# main_board3.net
KiCad netlist of a schematic drawn in EAGLE
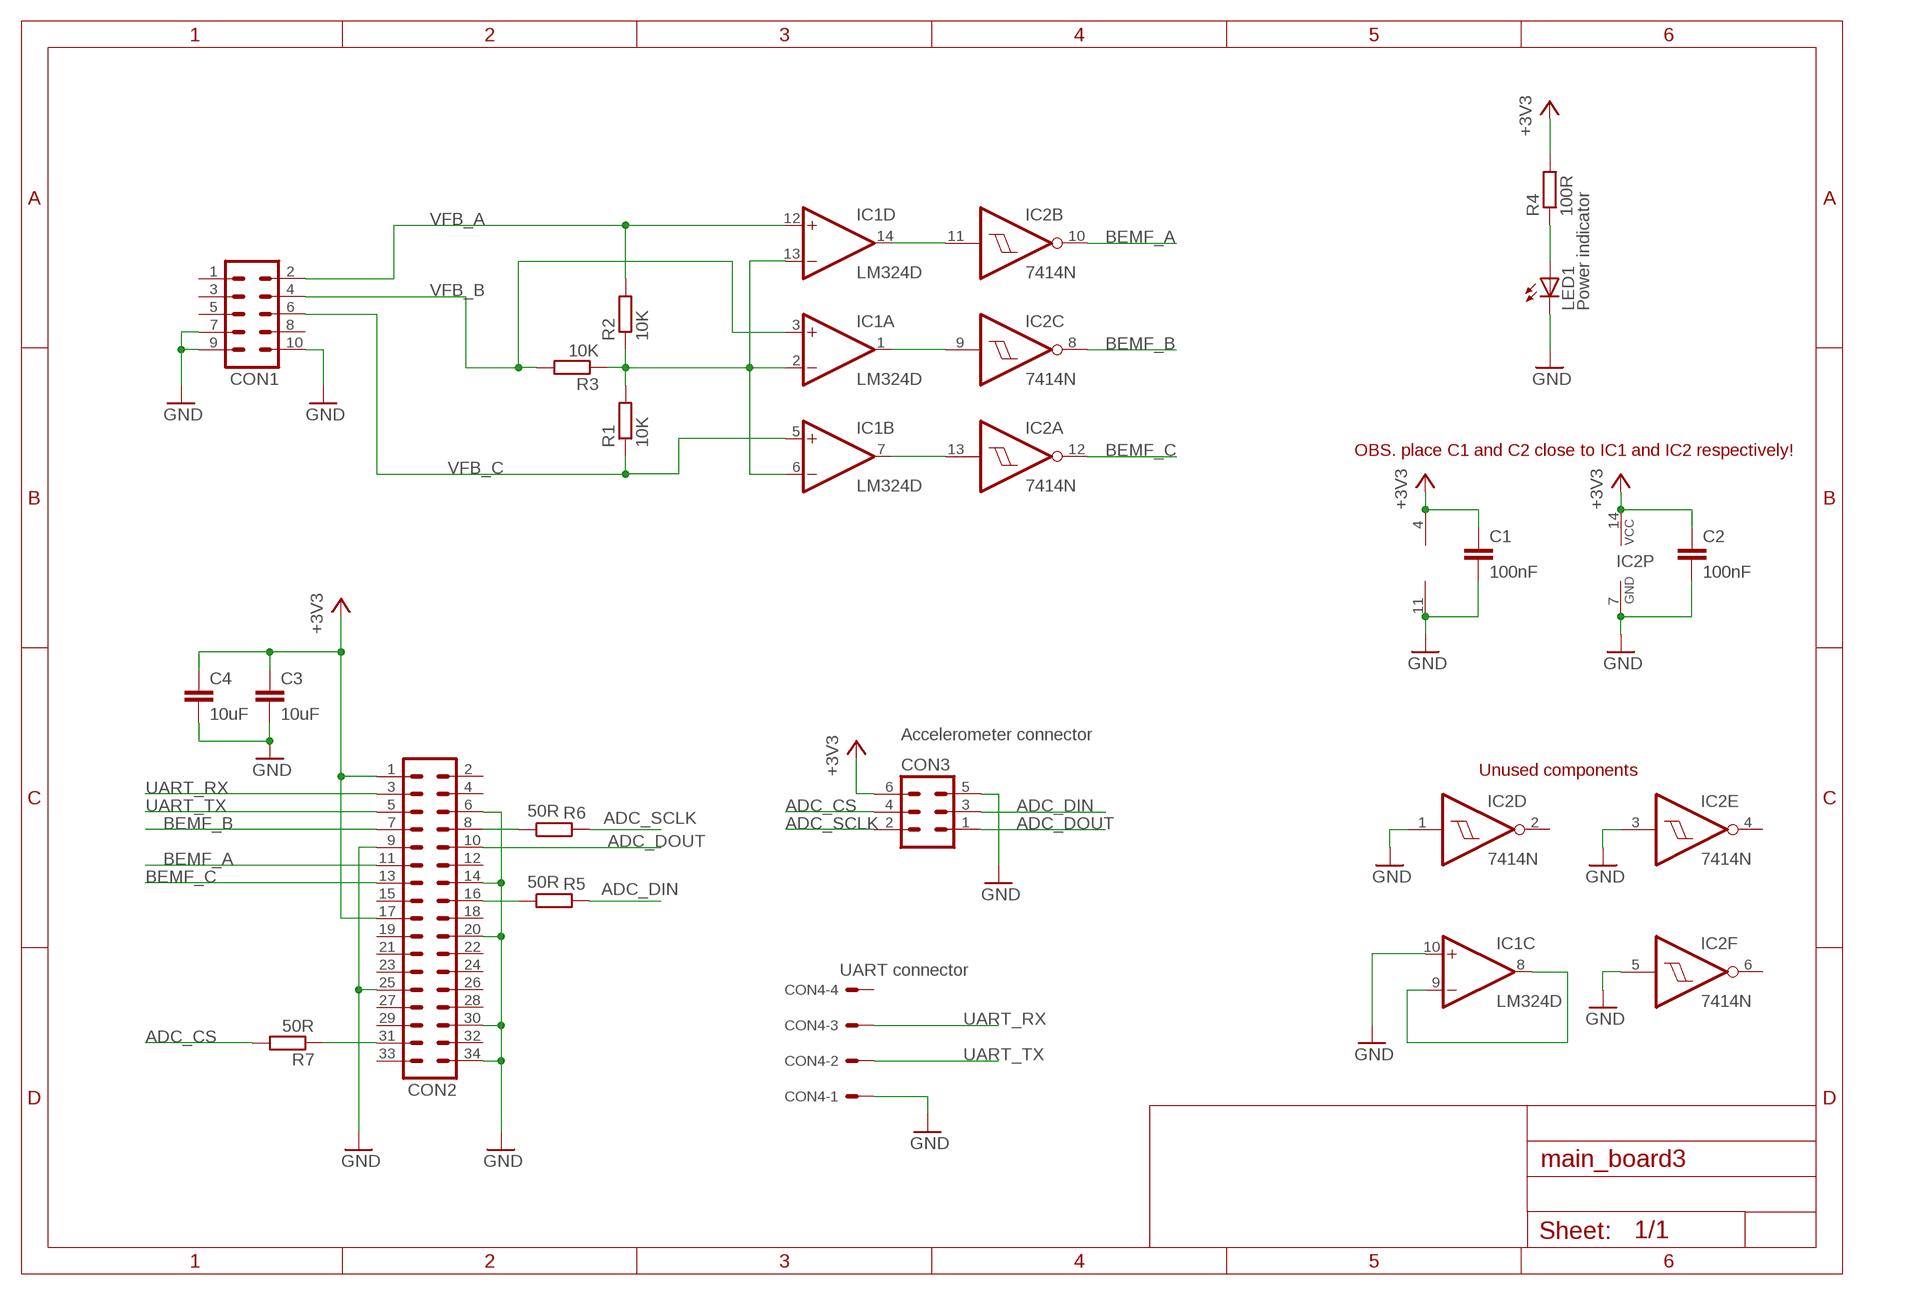
[diagram p0: schematic, sheet 1]

(export (version "E")
  (design (tool "Eeschema 10.0.6"))
  (components
    (comp (ref "C1")
      (value "100nF")
      (footprint "eagle-import:C0805K")
      (libsource (lib "eagle-import") (part "C-EUC0805K"))
    )
    (comp (ref "C2")
      (value "100nF")
      (footprint "eagle-import:C0805K")
      (libsource (lib "eagle-import") (part "C-EUC0805K"))
    )
    (comp (ref "C3")
      (value "10uF")
      (footprint "eagle-import:C1206K")
      (libsource (lib "eagle-import") (part "C-EUC1206K"))
    )
    (comp (ref "C4")
      (value "10uF")
      (footprint "eagle-import:C1206K")
      (libsource (lib "eagle-import") (part "C-EUC1206K"))
    )
    (comp (ref "CON1")
      (value "MA05-2")
      (footprint "eagle-import:MA05-2")
      (libsource (lib "eagle-import") (part "MA05-2"))
    )
    (comp (ref "CON2")
      (value "MA17-2")
      (footprint "eagle-import:MA17-2")
      (libsource (lib "eagle-import") (part "MA17-2"))
    )
    (comp (ref "CON3")
      (value "Accelerometer connector")
      (footprint "eagle-import:ML6")
      (libsource (lib "eagle-import") (part "ML6"))
    )
    (comp (ref "CON4")
      (value "UART connector")
      (footprint "eagle-import:6410-04")
      (libsource (lib "eagle-import") (part "22-?-0427-2041"))
    )
    (comp (ref "IC1")
      (value "LM324D")
      (footprint "eagle-import:SO14")
      (libsource (lib "eagle-import") (part "LM324D"))
    )
    (comp (ref "IC2")
      (value "7414N")
      (footprint "eagle-import:DIL14")
      (libsource (lib "eagle-import") (part "7414N"))
    )
    (comp (ref "LED1")
      (value "Power indicator")
      (footprint "eagle-import:CHIP-LED0805")
      (libsource (lib "eagle-import") (part "LEDCHIP-LED0805"))
    )
    (comp (ref "R1")
      (value "10K")
      (footprint "eagle-import:R0805")
      (libsource (lib "eagle-import") (part "R-EU_R0805"))
    )
    (comp (ref "R2")
      (value "10K")
      (footprint "eagle-import:R0805")
      (libsource (lib "eagle-import") (part "R-EU_R0805"))
    )
    (comp (ref "R3")
      (value "10K")
      (footprint "eagle-import:R0805")
      (libsource (lib "eagle-import") (part "R-EU_R0805"))
    )
    (comp (ref "R4")
      (value "100R")
      (footprint "eagle-import:R0805")
      (libsource (lib "eagle-import") (part "R-EU_R0805"))
    )
    (comp (ref "R5")
      (value "50R")
      (footprint "eagle-import:R0805")
      (libsource (lib "eagle-import") (part "R-EU_R0805"))
    )
    (comp (ref "R6")
      (value "50R")
      (footprint "eagle-import:R0805")
      (libsource (lib "eagle-import") (part "R-EU_R0805"))
    )
    (comp (ref "R7")
      (value "50R")
      (footprint "eagle-import:R0805")
      (libsource (lib "eagle-import") (part "R-EU_R0805"))
    )
  )
  (nets
    (net (code "1") (name "+3V3") (class "Default")
      (node (ref "C1") (pin "1") (pinfunction "1_1") (pintype "passive"))
      (node (ref "C2") (pin "1") (pinfunction "1_1") (pintype "passive"))
      (node (ref "C3") (pin "1") (pinfunction "1_1") (pintype "passive"))
      (node (ref "C4") (pin "1") (pinfunction "1_1") (pintype "passive"))
      (node (ref "CON2") (pin "1") (pinfunction "1_1") (pintype "passive"))
      (node (ref "CON2") (pin "17") (pinfunction "17_17") (pintype "passive"))
      (node (ref "CON3") (pin "6") (pinfunction "6_6") (pintype "passive"))
      (node (ref "IC1") (pin "4") (pinfunction "V+_4") (pintype "power_in"))
      (node (ref "IC2") (pin "14") (pinfunction "VCC_14") (pintype "power_in"))
      (node (ref "R4") (pin "2") (pinfunction "2_2") (pintype "passive"))
    )
    (net (code "2") (name "/ADC_CS") (class "Default")
      (node (ref "CON3") (pin "4") (pinfunction "4_4") (pintype "passive"))
      (node (ref "R7") (pin "2") (pinfunction "2_2") (pintype "passive"))
    )
    (net (code "3") (name "/ADC_DIN") (class "Default")
      (node (ref "CON3") (pin "3") (pinfunction "3_3") (pintype "passive"))
      (node (ref "R5") (pin "2") (pinfunction "2_2") (pintype "passive"))
    )
    (net (code "4") (name "/ADC_DOUT") (class "Default")
      (node (ref "CON2") (pin "10") (pinfunction "10_10") (pintype "passive"))
      (node (ref "CON3") (pin "1") (pinfunction "1_1") (pintype "passive"))
    )
    (net (code "5") (name "/ADC_SCLK") (class "Default")
      (node (ref "CON3") (pin "2") (pinfunction "2_2") (pintype "passive"))
      (node (ref "R6") (pin "2") (pinfunction "2_2") (pintype "passive"))
    )
    (net (code "6") (name "/BEMF_A") (class "Default")
      (node (ref "CON2") (pin "11") (pinfunction "11_11") (pintype "passive"))
      (node (ref "IC2") (pin "10") (pinfunction "O_10") (pintype "output"))
    )
    (net (code "7") (name "/BEMF_B") (class "Default")
      (node (ref "CON2") (pin "7") (pinfunction "7_7") (pintype "passive"))
      (node (ref "IC2") (pin "8") (pinfunction "O_8") (pintype "output"))
    )
    (net (code "8") (name "/BEMF_C") (class "Default")
      (node (ref "CON2") (pin "13") (pinfunction "13_13") (pintype "passive"))
      (node (ref "IC2") (pin "12") (pinfunction "O_12") (pintype "output"))
    )
    (net (code "9") (name "/UART_RX") (class "Default")
      (node (ref "CON2") (pin "3") (pinfunction "3_3") (pintype "passive"))
      (node (ref "CON4") (pin "3") (pinfunction "S_3") (pintype "passive"))
    )
    (net (code "10") (name "/UART_TX") (class "Default")
      (node (ref "CON2") (pin "5") (pinfunction "5_5") (pintype "passive"))
      (node (ref "CON4") (pin "2") (pinfunction "S_2") (pintype "passive"))
    )
    (net (code "11") (name "/VFB_A") (class "Default")
      (node (ref "CON1") (pin "2") (pinfunction "2_2") (pintype "passive"))
      (node (ref "IC1") (pin "12") (pinfunction "+IN_12") (pintype "input"))
      (node (ref "R2") (pin "2") (pinfunction "2_2") (pintype "passive"))
    )
    (net (code "12") (name "/VFB_B") (class "Default")
      (node (ref "CON1") (pin "4") (pinfunction "4_4") (pintype "passive"))
      (node (ref "IC1") (pin "3") (pinfunction "+IN_3") (pintype "input"))
      (node (ref "R3") (pin "2") (pinfunction "2_2") (pintype "passive"))
    )
    (net (code "13") (name "/VFB_C") (class "Default")
      (node (ref "CON1") (pin "6") (pinfunction "6_6") (pintype "passive"))
      (node (ref "IC1") (pin "5") (pinfunction "+IN_5") (pintype "input"))
      (node (ref "R1") (pin "1") (pinfunction "1_1") (pintype "passive"))
    )
    (net (code "14") (name "GND") (class "Default")
      (node (ref "C1") (pin "2") (pinfunction "2_2") (pintype "passive"))
      (node (ref "C2") (pin "2") (pinfunction "2_2") (pintype "passive"))
      (node (ref "C3") (pin "2") (pinfunction "2_2") (pintype "passive"))
      (node (ref "C4") (pin "2") (pinfunction "2_2") (pintype "passive"))
      (node (ref "CON1") (pin "10") (pinfunction "10_10") (pintype "passive"))
      (node (ref "CON1") (pin "7") (pinfunction "7_7") (pintype "passive"))
      (node (ref "CON1") (pin "9") (pinfunction "9_9") (pintype "passive"))
      (node (ref "CON2") (pin "14") (pinfunction "14_14") (pintype "passive"))
      (node (ref "CON2") (pin "20") (pinfunction "20_20") (pintype "passive"))
      (node (ref "CON2") (pin "25") (pinfunction "25_25") (pintype "passive"))
      (node (ref "CON2") (pin "30") (pinfunction "30_30") (pintype "passive"))
      (node (ref "CON2") (pin "34") (pinfunction "34_34") (pintype "passive"))
      (node (ref "CON2") (pin "6") (pinfunction "6_6") (pintype "passive"))
      (node (ref "CON2") (pin "9") (pinfunction "9_9") (pintype "passive"))
      (node (ref "CON3") (pin "5") (pinfunction "5_5") (pintype "passive"))
      (node (ref "CON4") (pin "1") (pinfunction "S_1") (pintype "passive"))
      (node (ref "IC1") (pin "10") (pinfunction "+IN_10") (pintype "input"))
      (node (ref "IC1") (pin "11") (pinfunction "V-_11") (pintype "power_in"))
      (node (ref "IC2") (pin "1") (pinfunction "I_1") (pintype "input"))
      (node (ref "IC2") (pin "3") (pinfunction "I_3") (pintype "input"))
      (node (ref "IC2") (pin "5") (pinfunction "I_5") (pintype "input"))
      (node (ref "IC2") (pin "7") (pinfunction "GND_7") (pintype "power_in"))
      (node (ref "LED1") (pin "C") (pinfunction "C_C") (pintype "passive"))
    )
    (net (code "15") (name "Net-(CON2-Pad8)") (class "Default")
      (node (ref "CON2") (pin "8") (pinfunction "8_8") (pintype "passive"))
      (node (ref "R6") (pin "1") (pinfunction "1_1") (pintype "passive"))
    )
    (net (code "16") (name "Net-(CON2-Pad16)") (class "Default")
      (node (ref "CON2") (pin "16") (pinfunction "16_16") (pintype "passive"))
      (node (ref "R5") (pin "1") (pinfunction "1_1") (pintype "passive"))
    )
    (net (code "17") (name "Net-(CON2-Pad31)") (class "Default")
      (node (ref "CON2") (pin "31") (pinfunction "31_31") (pintype "passive"))
      (node (ref "R7") (pin "1") (pinfunction "1_1") (pintype "passive"))
    )
    (net (code "18") (name "Net-(IC1A--IN)") (class "Default")
      (node (ref "IC1") (pin "13") (pinfunction "-IN_13") (pintype "input"))
      (node (ref "IC1") (pin "2") (pinfunction "-IN_2") (pintype "input"))
      (node (ref "IC1") (pin "6") (pinfunction "-IN_6") (pintype "input"))
      (node (ref "R1") (pin "2") (pinfunction "2_2") (pintype "passive"))
      (node (ref "R2") (pin "1") (pinfunction "1_1") (pintype "passive"))
      (node (ref "R3") (pin "1") (pinfunction "1_1") (pintype "passive"))
    )
    (net (code "19") (name "Net-(IC1A-OUT)") (class "Default")
      (node (ref "IC1") (pin "1") (pinfunction "OUT_1") (pintype "output"))
      (node (ref "IC2") (pin "9") (pinfunction "I_9") (pintype "input"))
    )
    (net (code "20") (name "Net-(IC1B-OUT)") (class "Default")
      (node (ref "IC1") (pin "7") (pinfunction "OUT_7") (pintype "output"))
      (node (ref "IC2") (pin "13") (pinfunction "I_13") (pintype "input"))
    )
    (net (code "21") (name "Net-(IC1C--IN)") (class "Default")
      (node (ref "IC1") (pin "8") (pinfunction "OUT_8") (pintype "output"))
      (node (ref "IC1") (pin "9") (pinfunction "-IN_9") (pintype "input"))
    )
    (net (code "22") (name "Net-(IC1D-OUT)") (class "Default")
      (node (ref "IC1") (pin "14") (pinfunction "OUT_14") (pintype "output"))
      (node (ref "IC2") (pin "11") (pinfunction "I_11") (pintype "input"))
    )
    (net (code "23") (name "Net-(LED1-PadA)") (class "Default")
      (node (ref "LED1") (pin "A") (pinfunction "A_A") (pintype "passive"))
      (node (ref "R4") (pin "1") (pinfunction "1_1") (pintype "passive"))
    )
    (net (code "24") (name "unconnected-(CON1-Pad1)") (class "Default")
      (node (ref "CON1") (pin "1") (pinfunction "1_1") (pintype "passive"))
    )
    (net (code "25") (name "unconnected-(CON1-Pad3)") (class "Default")
      (node (ref "CON1") (pin "3") (pinfunction "3_3") (pintype "passive"))
    )
    (net (code "26") (name "unconnected-(CON1-Pad5)") (class "Default")
      (node (ref "CON1") (pin "5") (pinfunction "5_5") (pintype "passive"))
    )
    (net (code "27") (name "unconnected-(CON1-Pad8)") (class "Default")
      (node (ref "CON1") (pin "8") (pinfunction "8_8") (pintype "passive"))
    )
    (net (code "28") (name "unconnected-(CON2-Pad2)") (class "Default")
      (node (ref "CON2") (pin "2") (pinfunction "2_2") (pintype "passive"))
    )
    (net (code "29") (name "unconnected-(CON2-Pad4)") (class "Default")
      (node (ref "CON2") (pin "4") (pinfunction "4_4") (pintype "passive"))
    )
    (net (code "30") (name "unconnected-(CON2-Pad12)") (class "Default")
      (node (ref "CON2") (pin "12") (pinfunction "12_12") (pintype "passive"))
    )
    (net (code "31") (name "unconnected-(CON2-Pad15)") (class "Default")
      (node (ref "CON2") (pin "15") (pinfunction "15_15") (pintype "passive"))
    )
    (net (code "32") (name "unconnected-(CON2-Pad18)") (class "Default")
      (node (ref "CON2") (pin "18") (pinfunction "18_18") (pintype "passive"))
    )
    (net (code "33") (name "unconnected-(CON2-Pad19)") (class "Default")
      (node (ref "CON2") (pin "19") (pinfunction "19_19") (pintype "passive"))
    )
    (net (code "34") (name "unconnected-(CON2-Pad21)") (class "Default")
      (node (ref "CON2") (pin "21") (pinfunction "21_21") (pintype "passive"))
    )
    (net (code "35") (name "unconnected-(CON2-Pad22)") (class "Default")
      (node (ref "CON2") (pin "22") (pinfunction "22_22") (pintype "passive"))
    )
    (net (code "36") (name "unconnected-(CON2-Pad23)") (class "Default")
      (node (ref "CON2") (pin "23") (pinfunction "23_23") (pintype "passive"))
    )
    (net (code "37") (name "unconnected-(CON2-Pad24)") (class "Default")
      (node (ref "CON2") (pin "24") (pinfunction "24_24") (pintype "passive"))
    )
    (net (code "38") (name "unconnected-(CON2-Pad26)") (class "Default")
      (node (ref "CON2") (pin "26") (pinfunction "26_26") (pintype "passive"))
    )
    (net (code "39") (name "unconnected-(CON2-Pad27)") (class "Default")
      (node (ref "CON2") (pin "27") (pinfunction "27_27") (pintype "passive"))
    )
    (net (code "40") (name "unconnected-(CON2-Pad28)") (class "Default")
      (node (ref "CON2") (pin "28") (pinfunction "28_28") (pintype "passive"))
    )
    (net (code "41") (name "unconnected-(CON2-Pad29)") (class "Default")
      (node (ref "CON2") (pin "29") (pinfunction "29_29") (pintype "passive"))
    )
    (net (code "42") (name "unconnected-(CON2-Pad32)") (class "Default")
      (node (ref "CON2") (pin "32") (pinfunction "32_32") (pintype "passive"))
    )
    (net (code "43") (name "unconnected-(CON2-Pad33)") (class "Default")
      (node (ref "CON2") (pin "33") (pinfunction "33_33") (pintype "passive"))
    )
    (net (code "44") (name "unconnected-(CON4D-S-Pad4)") (class "Default")
      (node (ref "CON4") (pin "4") (pinfunction "S_4") (pintype "passive"))
    )
    (net (code "45") (name "unconnected-(IC2D-O-Pad2)") (class "Default")
      (node (ref "IC2") (pin "2") (pinfunction "O_2") (pintype "output"))
    )
    (net (code "46") (name "unconnected-(IC2E-O-Pad4)") (class "Default")
      (node (ref "IC2") (pin "4") (pinfunction "O_4") (pintype "output"))
    )
    (net (code "47") (name "unconnected-(IC2F-O-Pad6)") (class "Default")
      (node (ref "IC2") (pin "6") (pinfunction "O_6") (pintype "output"))
    )
  )
)
